# SCH_Satlla_4_Motor_plate_2023-01-29.net
KiCad netlist of a schematic drawn in EasyEDA
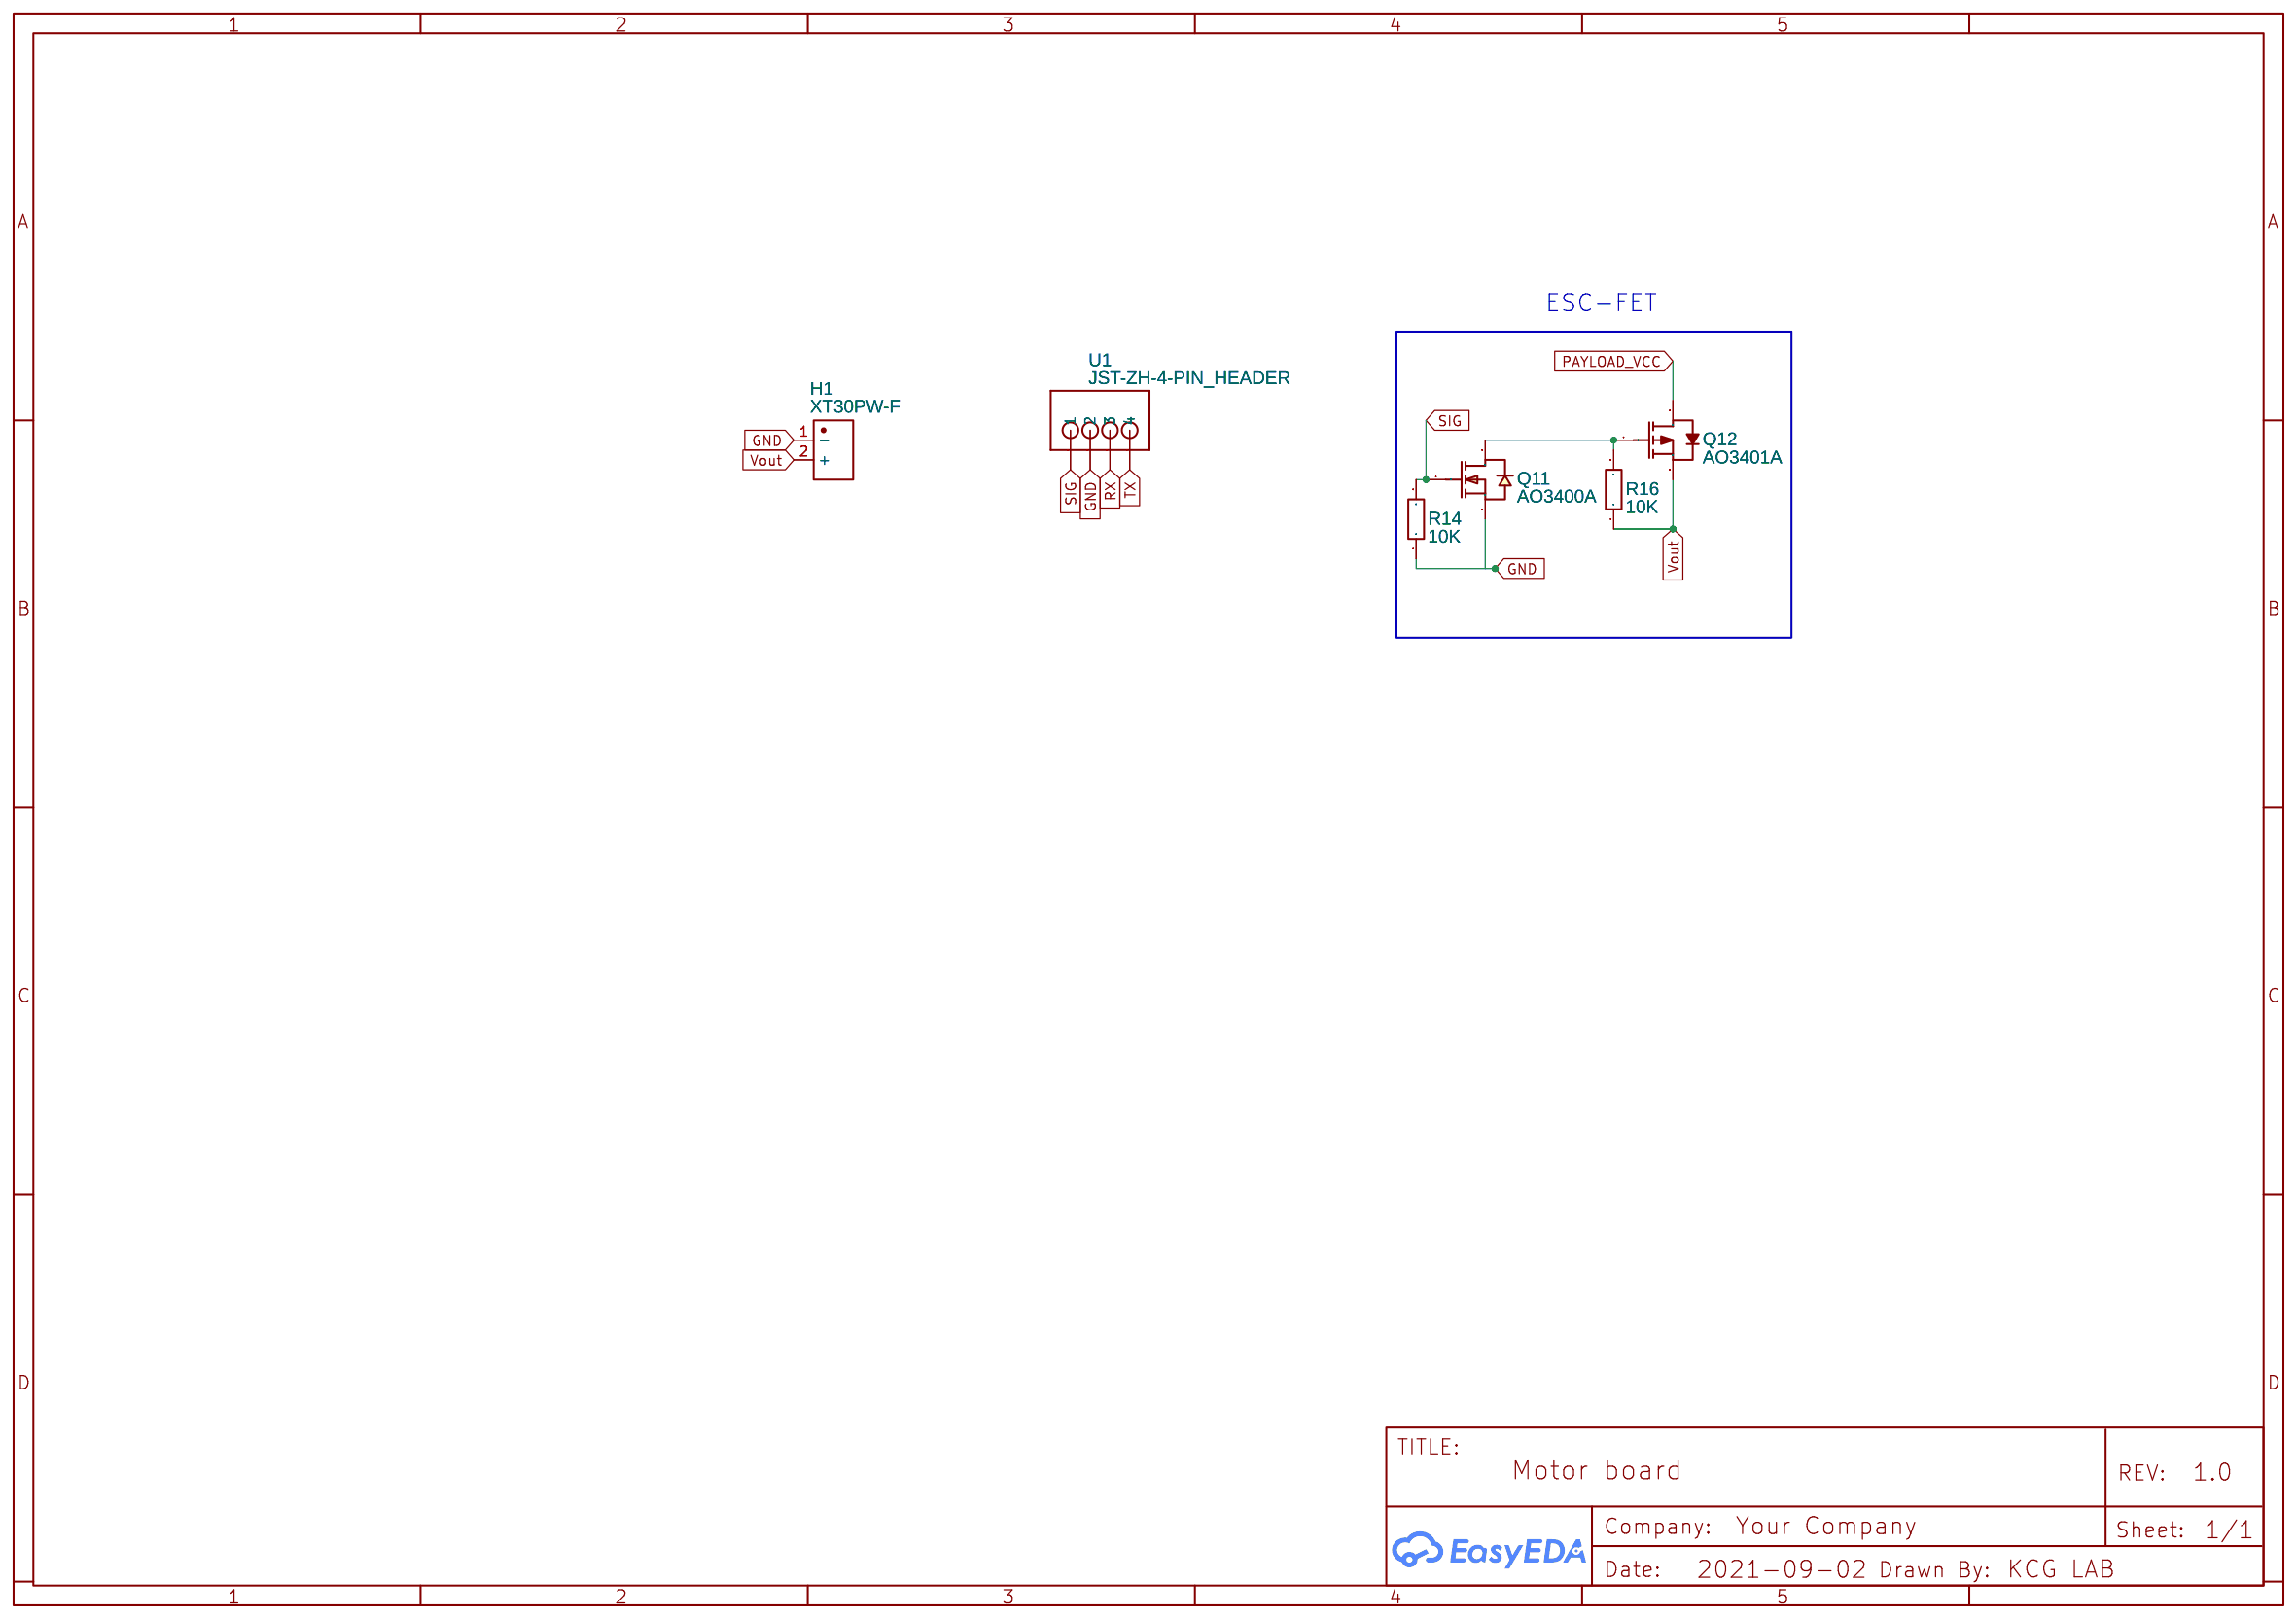
[diagram p0: schematic sheet]

(export (version "E")
  (design (tool "Eeschema 10.0.6"))
  (components
    (comp (ref "H1")
      (value "XT30PW-F")
      (fields (field (name "BOM_Manufacturer Part") "XT30PW") (field (name "BOM_Supplier Part") "1075324"))
      (libsource (lib "") (part "XT30PW-F"))
    )
    (comp (ref "Q11")
      (value "AO3400A")
      (fields (field (name "BOM_Supplier Part") "C20917"))
      (libsource (lib "") (part "AO3400A"))
    )
    (comp (ref "Q12")
      (value "AO3401A")
      (fields (field (name "BOM_Supplier Part") "C15127"))
      (libsource (lib "") (part "AO3401A"))
    )
    (comp (ref "R14")
      (value "10K")
      (fields
        (field (name "BOM_Manufacturer Part") "0603WAF1002T5E")
        (field (name "BOM_Supplier Part") "C25804")
      )
      (libsource (lib "") (part "0603WAF1002T5E"))
    )
    (comp (ref "R16")
      (value "10K")
      (fields
        (field (name "BOM_Manufacturer Part") "0603WAF1002T5E")
        (field (name "BOM_Supplier Part") "C25804")
      )
      (libsource (lib "") (part "0603WAF1002T5E"))
    )
    (comp (ref "U1") (value "JST-ZH-4-PIN_HEADER") (libsource (lib "") (part "JST-ZH-4-PIN_HEADER")))
  )
  (nets
    (net (code "1") (name "GND") (class "Default")
      (node (ref "H1") (pin "1") (pinfunction "-_1") (pintype "unspecified"))
      (node (ref "Q11") (pin "2") (pinfunction "S_2") (pintype "unspecified"))
      (node (ref "R14") (pin "1") (pinfunction "1_1") (pintype "input"))
      (node (ref "U1") (pin "P2") (pinfunction "2_P2") (pintype "unspecified"))
    )
    (net (code "2") (name "Net-(Q11-D)") (class "Default")
      (node (ref "Q11") (pin "3") (pinfunction "D_3") (pintype "unspecified"))
      (node (ref "Q12") (pin "1") (pinfunction "G_1") (pintype "unspecified"))
      (node (ref "R16") (pin "2") (pinfunction "2_2") (pintype "input"))
    )
    (net (code "3") (name "PAYLOAD_VCC") (class "Default")
      (node (ref "Q12") (pin "3") (pinfunction "D_3") (pintype "unspecified"))
    )
    (net (code "4") (name "RX") (class "Default")
      (node (ref "U1") (pin "P3") (pinfunction "3_P3") (pintype "unspecified"))
    )
    (net (code "5") (name "SIG") (class "Default")
      (node (ref "Q11") (pin "1") (pinfunction "G_1") (pintype "unspecified"))
      (node (ref "R14") (pin "2") (pinfunction "2_2") (pintype "input"))
      (node (ref "U1") (pin "P1") (pinfunction "1_P1") (pintype "unspecified"))
    )
    (net (code "6") (name "TX") (class "Default")
      (node (ref "U1") (pin "P4") (pinfunction "4_P4") (pintype "unspecified"))
    )
    (net (code "7") (name "Vout") (class "Default")
      (node (ref "H1") (pin "2") (pinfunction "+_2") (pintype "unspecified"))
      (node (ref "Q12") (pin "2") (pinfunction "S_2") (pintype "unspecified"))
      (node (ref "R16") (pin "1") (pinfunction "1_1") (pintype "input"))
    )
  )
)
